# Fans.net
KiCad netlist of a schematic drawn in Altium Designer
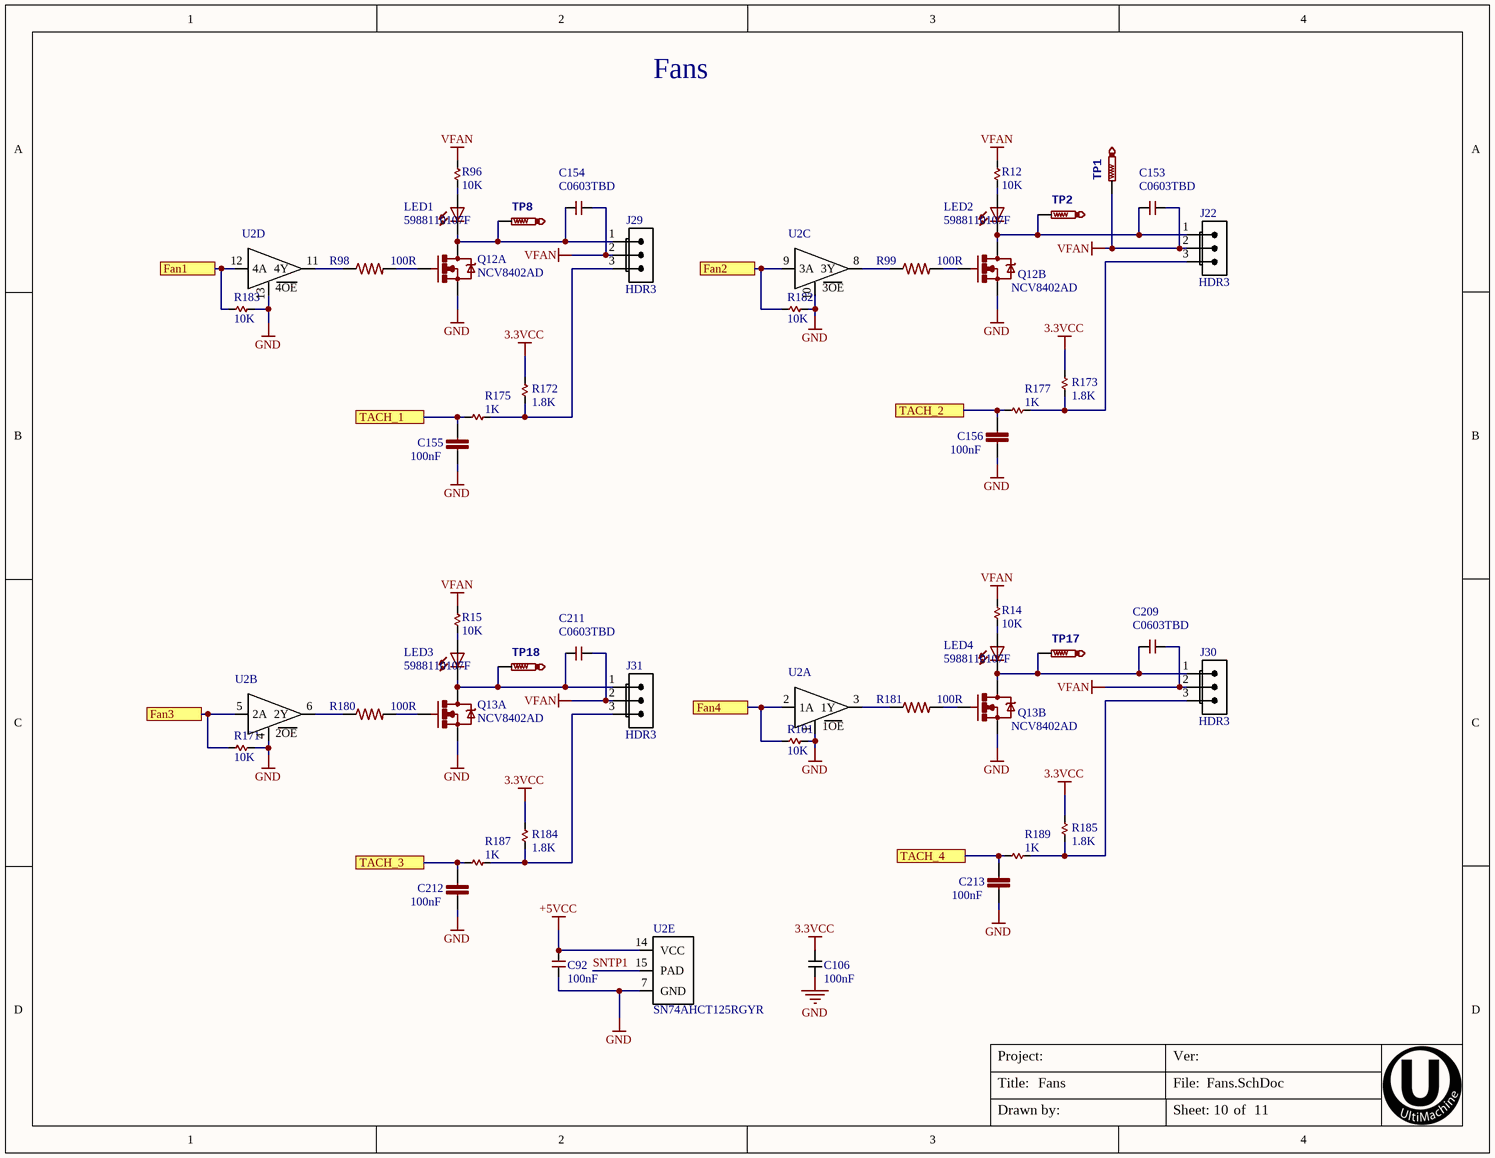
[diagram p0: Fans.SchDoc]

(export (version "E")
  (design (tool "Eeschema 10.0.6"))
  (components
    (comp (ref "C92")
      (value "100nF")
      (footprint "C0402")
      (description "CAP CER 0402 100nF 16V 10% X7R")
      (fields (field (name "MANUFACTURER") "Murata") (field (name "PART") "GRM155R71C104KA88D"))
      (libsource (lib "Capacitors") (part "100nF 0402 16V X7R"))
    )
    (comp (ref "C106")
      (value "100nF")
      (footprint "C0201 Large Pads")
      (description "CAP CER 0.1UF 6.3V 10% X5R 0201")
      (fields (field (name "PART") "CL03A104KQ3NNNC") (field (name "MANUFACTURER") "Samsung"))
      (libsource (lib "Capacitors") (part "100nF 6.3V X5R 0201"))
    )
    (comp (ref "C153")
      (value "C0603TBD")
      (footprint "C0603")
      (description "Capacitor Non Polarized")
      (fields (field (name "PART") "DNI-C0603TBD"))
      (libsource (lib "Capacitors") (part "C0603TBD"))
    )
    (comp (ref "C154")
      (value "C0603TBD")
      (footprint "C0603")
      (description "Capacitor Non Polarized")
      (fields (field (name "PART") "DNI-C0603TBD"))
      (libsource (lib "Capacitors") (part "C0603TBD"))
    )
    (comp (ref "C155")
      (value "100nF")
      (footprint "C0402")
      (description "CAP CER 0402 100nF 16V 10% X7R")
      (fields (field (name "MANUFACTURER") "Murata") (field (name "PART") "GRM155R71C104KA88D"))
      (libsource (lib "3Delight") (part "GRM155R71C104KA88D"))
    )
    (comp (ref "C156")
      (value "100nF")
      (footprint "C0402")
      (description "CAP CER 0402 100nF 16V 10% X7R")
      (fields (field (name "MANUFACTURER") "Murata") (field (name "PART") "GRM155R71C104KA88D"))
      (libsource (lib "3Delight") (part "GRM155R71C104KA88D"))
    )
    (comp (ref "C209")
      (value "C0603TBD")
      (footprint "C0603")
      (description "Capacitor Non Polarized")
      (fields (field (name "PART") "DNI-C0603TBD"))
      (libsource (lib "Capacitors") (part "C0603TBD"))
    )
    (comp (ref "C211")
      (value "C0603TBD")
      (footprint "C0603")
      (description "Capacitor Non Polarized")
      (fields (field (name "PART") "DNI-C0603TBD"))
      (libsource (lib "Capacitors") (part "C0603TBD"))
    )
    (comp (ref "C212")
      (value "100nF")
      (footprint "C0402")
      (description "CAP CER 0402 100nF 16V 10% X7R")
      (fields (field (name "MANUFACTURER") "Murata") (field (name "PART") "GRM155R71C104KA88D"))
      (libsource (lib "3Delight") (part "GRM155R71C104KA88D"))
    )
    (comp (ref "C213")
      (value "100nF")
      (footprint "C0402")
      (description "CAP CER 0402 100nF 16V 10% X7R")
      (fields (field (name "MANUFACTURER") "Murata") (field (name "PART") "GRM155R71C104KA88D"))
      (libsource (lib "3Delight") (part "GRM155R71C104KA88D"))
    )
    (comp (ref "J22")
      (value "HDR3")
      (footprint "70543-02 PIN-IN-PASTE")
      (description "3 Positions Header, Shrouded Connector 0.100\" (2.54mm) Through Hole Gold - Pin in Paste")
      (fields (field (name "MANUFACTURER") "Molex") (field (name "PART") "0705430002"))
      (libsource (lib "Connectors") (part "CONN 3POS VERT 0.1{dblquote} SHRD LOCKING PIP"))
    )
    (comp (ref "J29")
      (value "HDR3")
      (footprint "70543-02 PIN-IN-PASTE")
      (description "3 Positions Header, Shrouded Connector 0.100\" (2.54mm) Through Hole Gold - Pin in Paste")
      (fields (field (name "MANUFACTURER") "Molex") (field (name "PART") "0705430002"))
      (libsource (lib "Connectors") (part "CONN 3POS VERT 0.1{dblquote} SHRD LOCKING PIP"))
    )
    (comp (ref "J30")
      (value "HDR3")
      (footprint "70543-02 PIN-IN-PASTE")
      (description "3 Positions Header, Shrouded Connector 0.100\" (2.54mm) Through Hole Gold - Pin in Paste")
      (fields (field (name "MANUFACTURER") "Molex") (field (name "PART") "0705430002"))
      (libsource (lib "Connectors") (part "CONN 3POS VERT 0.1{dblquote} SHRD LOCKING PIP"))
    )
    (comp (ref "J31")
      (value "HDR3")
      (footprint "70543-02 PIN-IN-PASTE")
      (description "3 Positions Header, Shrouded Connector 0.100\" (2.54mm) Through Hole Gold - Pin in Paste")
      (fields (field (name "MANUFACTURER") "Molex") (field (name "PART") "0705430002"))
      (libsource (lib "Connectors") (part "CONN 3POS VERT 0.1{dblquote} SHRD LOCKING PIP"))
    )
    (comp (ref "LED1")
      (value "RED")
      (footprint "LED2012120")
      (description "LED 0805 Red")
      (fields
        (field (name "MANUFACTURER") "Dialight")
        (field (name "PART") "5988110107F")
        (field (name "TOLERANCE") "NA")
      )
      (libsource (lib "3Delight") (part "5988110107F"))
    )
    (comp (ref "LED2")
      (value "RED")
      (footprint "LED2012120")
      (description "LED 0805 Red")
      (fields
        (field (name "MANUFACTURER") "Dialight")
        (field (name "PART") "5988110107F")
        (field (name "TOLERANCE") "NA")
      )
      (libsource (lib "3Delight") (part "5988110107F"))
    )
    (comp (ref "LED3")
      (value "RED")
      (footprint "LED2012120")
      (description "LED 0805 Red")
      (fields
        (field (name "MANUFACTURER") "Dialight")
        (field (name "PART") "5988110107F")
        (field (name "TOLERANCE") "NA")
      )
      (libsource (lib "3Delight") (part "5988110107F"))
    )
    (comp (ref "LED4")
      (value "RED")
      (footprint "LED2012120")
      (description "LED 0805 Red")
      (fields
        (field (name "MANUFACTURER") "Dialight")
        (field (name "PART") "5988110107F")
        (field (name "TOLERANCE") "NA")
      )
      (libsource (lib "3Delight") (part "5988110107F"))
    )
    (comp (ref "Q12")
      (value "NCV8402AD")
      (footprint "NCV8402AD-SOIC8")
      (description "IC DVR LOW SIDE 8-SOIC")
      (fields (field (name "MANUFACTURER") "On Semi") (field (name "PART") "NCV8402ADDR2G"))
      (libsource (lib "Transistors") (part "NCV8402AD"))
    )
    (comp (ref "Q13")
      (value "NCV8402AD")
      (footprint "NCV8402AD-SOIC8")
      (description "IC DVR LOW SIDE 8-SOIC")
      (fields (field (name "MANUFACTURER") "On Semi") (field (name "PART") "NCV8402ADDR2G"))
      (libsource (lib "Transistors") (part "NCV8402AD"))
    )
    (comp (ref "R12")
      (value "10K")
      (footprint "R0402")
      (description "RES SMD 10K OHM 1% 1/16W 0402")
      (fields (field (name "MANUFACTURER") "Yageo") (field (name "PART") "RC0402FR-0710KP"))
      (libsource (lib "Resistors") (part "10k 1% 0402"))
    )
    (comp (ref "R14")
      (value "10K")
      (footprint "R0402")
      (description "RES SMD 10K OHM 1% 1/16W 0402")
      (fields (field (name "MANUFACTURER") "Yageo") (field (name "PART") "RC0402FR-0710KP"))
      (libsource (lib "Resistors") (part "10k 1% 0402"))
    )
    (comp (ref "R15")
      (value "10K")
      (footprint "R0402")
      (description "RES SMD 10K OHM 1% 1/16W 0402")
      (fields (field (name "MANUFACTURER") "Yageo") (field (name "PART") "RC0402FR-0710KP"))
      (libsource (lib "Resistors") (part "10k 1% 0402"))
    )
    (comp (ref "R96")
      (value "10K")
      (footprint "R0402")
      (description "RES SMD 10K OHM 1% 1/16W 0402")
      (fields (field (name "MANUFACTURER") "Yageo") (field (name "PART") "RC0402FR-0710KP"))
      (libsource (lib "Resistors") (part "10k 1% 0402"))
    )
    (comp (ref "R98")
      (value "100R")
      (footprint "R0402")
      (description "RES SMD 100 OHM 1% 1/16W 0402")
      (fields (field (name "MANUFACTURER") "Yageo") (field (name "PART") "RC0402FR-07100RL"))
      (libsource (lib "Archim") (part "RES 100R 0402 1%"))
    )
    (comp (ref "R99")
      (value "100R")
      (footprint "R0402")
      (description "RES SMD 100 OHM 1% 1/16W 0402")
      (fields (field (name "MANUFACTURER") "Yageo") (field (name "PART") "RC0402FR-07100RL"))
      (libsource (lib "Archim") (part "RES 100R 0402 1%"))
    )
    (comp (ref "R101")
      (value "10K")
      (footprint "R0402")
      (description "RES SMD 10K OHM 1% 1/16W 0402")
      (fields (field (name "MANUFACTURER") "Yageo") (field (name "PART") "RC0402FR-0710KP"))
      (libsource (lib "Resistors") (part "10k 1% 0402"))
    )
    (comp (ref "R171")
      (value "10K")
      (footprint "R0402")
      (description "RES SMD 10K OHM 1% 1/16W 0402")
      (fields (field (name "MANUFACTURER") "Yageo") (field (name "PART") "RC0402FR-0710KP"))
      (libsource (lib "Resistors") (part "10k 1% 0402"))
    )
    (comp (ref "R172")
      (value "1.8K")
      (footprint "R0402")
      (description "RES SMD 1.8K OHM 1% 1/16W 0402")
      (fields (field (name "MANUFACTURER") "Yageo") (field (name "PART") "RC0402FR-071K8L"))
      (libsource (lib "3Delight") (part "RC0402FR-071K8L"))
    )
    (comp (ref "R173")
      (value "1.8K")
      (footprint "R0402")
      (description "RES SMD 1.8K OHM 1% 1/16W 0402")
      (fields (field (name "MANUFACTURER") "Yageo") (field (name "PART") "RC0402FR-071K8L"))
      (libsource (lib "3Delight") (part "RC0402FR-071K8L"))
    )
    (comp (ref "R175")
      (value "1K")
      (footprint "R0402")
      (description "RES SMD 1K OHM 1% 1/16W 0402")
      (fields (field (name "MANUFACTURER") "Yageo") (field (name "PART") "RC0402FR-071KL"))
      (libsource (lib "3Delight") (part "RC0402FR-071KL"))
    )
    (comp (ref "R177")
      (value "1K")
      (footprint "R0402")
      (description "RES SMD 1K OHM 1% 1/16W 0402")
      (fields (field (name "MANUFACTURER") "Yageo") (field (name "PART") "RC0402FR-071KL"))
      (libsource (lib "3Delight") (part "RC0402FR-071KL"))
    )
    (comp (ref "R180")
      (value "100R")
      (footprint "R0402")
      (description "RES SMD 100 OHM 1% 1/16W 0402")
      (fields (field (name "MANUFACTURER") "Yageo") (field (name "PART") "RC0402FR-07100RL"))
      (libsource (lib "Archim") (part "RES 100R 0402 1%"))
    )
    (comp (ref "R181")
      (value "100R")
      (footprint "R0402")
      (description "RES SMD 100 OHM 1% 1/16W 0402")
      (fields (field (name "MANUFACTURER") "Yageo") (field (name "PART") "RC0402FR-07100RL"))
      (libsource (lib "Archim") (part "RES 100R 0402 1%"))
    )
    (comp (ref "R182")
      (value "10K")
      (footprint "R0402")
      (description "RES SMD 10K OHM 1% 1/16W 0402")
      (fields (field (name "MANUFACTURER") "Yageo") (field (name "PART") "RC0402FR-0710KP"))
      (libsource (lib "Resistors") (part "10k 1% 0402"))
    )
    (comp (ref "R183")
      (value "10K")
      (footprint "R0402")
      (description "RES SMD 10K OHM 1% 1/16W 0402")
      (fields (field (name "MANUFACTURER") "Yageo") (field (name "PART") "RC0402FR-0710KP"))
      (libsource (lib "Resistors") (part "10k 1% 0402"))
    )
    (comp (ref "R184")
      (value "1.8K")
      (footprint "R0402")
      (description "RES SMD 1.8K OHM 1% 1/16W 0402")
      (fields (field (name "MANUFACTURER") "Yageo") (field (name "PART") "RC0402FR-071K8L"))
      (libsource (lib "3Delight") (part "RC0402FR-071K8L"))
    )
    (comp (ref "R185")
      (value "1.8K")
      (footprint "R0402")
      (description "RES SMD 1.8K OHM 1% 1/16W 0402")
      (fields (field (name "MANUFACTURER") "Yageo") (field (name "PART") "RC0402FR-071K8L"))
      (libsource (lib "3Delight") (part "RC0402FR-071K8L"))
    )
    (comp (ref "R187")
      (value "1K")
      (footprint "R0402")
      (description "RES SMD 1K OHM 1% 1/16W 0402")
      (fields (field (name "MANUFACTURER") "Yageo") (field (name "PART") "RC0402FR-071KL"))
      (libsource (lib "3Delight") (part "RC0402FR-071KL"))
    )
    (comp (ref "R189")
      (value "1K")
      (footprint "R0402")
      (description "RES SMD 1K OHM 1% 1/16W 0402")
      (fields (field (name "MANUFACTURER") "Yageo") (field (name "PART") "RC0402FR-071KL"))
      (libsource (lib "3Delight") (part "RC0402FR-071KL"))
    )
    (comp (ref "TP1")
      (value "TestPoint")
      (footprint "TP1-27")
      (description "Test Point")
      (libsource (lib "") (part "TestPoint_1"))
    )
    (comp (ref "TP2")
      (value "TestPoint")
      (footprint "TP1-27")
      (description "Test Point")
      (libsource (lib "3Delight") (part "TestPoint"))
    )
    (comp (ref "TP8")
      (value "TestPoint")
      (footprint "TP1-27")
      (description "Test Point")
      (libsource (lib "3Delight") (part "TestPoint"))
    )
    (comp (ref "TP17")
      (value "TestPoint")
      (footprint "TP1-27")
      (description "Test Point")
      (libsource (lib "3Delight") (part "TestPoint"))
    )
    (comp (ref "TP18")
      (value "TestPoint")
      (footprint "TP1-27")
      (description "Test Point")
      (libsource (lib "3Delight") (part "TestPoint"))
    )
    (comp (ref "U2")
      (value "SN74AHCT125RGYR")
      (footprint "QFN50P350X350X100_RGY_S-PVQFN-N14")
      (description "Quadruple Bus Buffer Gates With 3-State Outputs 14-VQFN -40 to 125")
      (fields (field (name "MANUFACTURER") "Texas Instruments") (field (name "TOLERANCE") "-NA-"))
      (libsource (lib "ICs-Logic") (part "SN74AHCT125"))
    )
  )
  (nets
    (net (code "1") (name "+5VCC") (class "Default")
      (node (ref "C92") (pin "2") (pinfunction "2_2") (pintype "passive"))
      (node (ref "U2") (pin "14") (pinfunction "VCC_14") (pintype "passive"))
    )
    (net (code "2") (name "/Fan1") (class "Default")
      (node (ref "R183") (pin "1") (pinfunction "1_1") (pintype "passive"))
      (node (ref "U2") (pin "12") (pinfunction "4A_12") (pintype "passive"))
    )
    (net (code "3") (name "/Fan2") (class "Default")
      (node (ref "R182") (pin "1") (pinfunction "1_1") (pintype "passive"))
      (node (ref "U2") (pin "9") (pinfunction "3A_9") (pintype "passive"))
    )
    (net (code "4") (name "/Fan3") (class "Default")
      (node (ref "R171") (pin "1") (pinfunction "1_1") (pintype "passive"))
      (node (ref "U2") (pin "5") (pinfunction "2A_5") (pintype "passive"))
    )
    (net (code "5") (name "/Fan4") (class "Default")
      (node (ref "R101") (pin "1") (pinfunction "1_1") (pintype "passive"))
      (node (ref "U2") (pin "2") (pinfunction "1A_2") (pintype "passive"))
    )
    (net (code "6") (name "/SNTP1") (class "Default")
      (node (ref "U2") (pin "15") (pinfunction "PAD_15") (pintype "passive"))
    )
    (net (code "7") (name "/TACH_1") (class "Default")
      (node (ref "C155") (pin "1") (pinfunction "1_1") (pintype "passive"))
      (node (ref "R175") (pin "1") (pinfunction "1_1") (pintype "passive"))
    )
    (net (code "8") (name "/TACH_2") (class "Default")
      (node (ref "C156") (pin "1") (pinfunction "1_1") (pintype "passive"))
      (node (ref "R177") (pin "1") (pinfunction "1_1") (pintype "passive"))
    )
    (net (code "9") (name "/TACH_3") (class "Default")
      (node (ref "C212") (pin "1") (pinfunction "1_1") (pintype "passive"))
      (node (ref "R187") (pin "1") (pinfunction "1_1") (pintype "passive"))
    )
    (net (code "10") (name "/TACH_4") (class "Default")
      (node (ref "C213") (pin "1") (pinfunction "1_1") (pintype "passive"))
      (node (ref "R189") (pin "1") (pinfunction "1_1") (pintype "passive"))
    )
    (net (code "11") (name "3.3VCC") (class "Default")
      (node (ref "C106") (pin "2") (pinfunction "2_2") (pintype "passive"))
      (node (ref "R172") (pin "2") (pinfunction "2_2") (pintype "passive"))
      (node (ref "R173") (pin "2") (pinfunction "2_2") (pintype "passive"))
      (node (ref "R184") (pin "2") (pinfunction "2_2") (pintype "passive"))
      (node (ref "R185") (pin "2") (pinfunction "2_2") (pintype "passive"))
    )
    (net (code "12") (name "GND") (class "Default")
      (node (ref "C106") (pin "1") (pinfunction "1_1") (pintype "passive"))
      (node (ref "C155") (pin "2") (pinfunction "2_2") (pintype "passive"))
      (node (ref "C156") (pin "2") (pinfunction "2_2") (pintype "passive"))
      (node (ref "C212") (pin "2") (pinfunction "2_2") (pintype "passive"))
      (node (ref "C213") (pin "2") (pinfunction "2_2") (pintype "passive"))
      (node (ref "C92") (pin "1") (pinfunction "1_1") (pintype "passive"))
      (node (ref "Q12") (pin "1") (pinfunction "S_1") (pintype "passive"))
      (node (ref "Q12") (pin "3") (pinfunction "S_3") (pintype "passive"))
      (node (ref "Q13") (pin "1") (pinfunction "S_1") (pintype "passive"))
      (node (ref "Q13") (pin "3") (pinfunction "S_3") (pintype "passive"))
      (node (ref "R101") (pin "2") (pinfunction "2_2") (pintype "passive"))
      (node (ref "R171") (pin "2") (pinfunction "2_2") (pintype "passive"))
      (node (ref "R182") (pin "2") (pinfunction "2_2") (pintype "passive"))
      (node (ref "R183") (pin "2") (pinfunction "2_2") (pintype "passive"))
      (node (ref "U2") (pin "1") (pinfunction "1OE_1") (pintype "passive"))
      (node (ref "U2") (pin "10") (pinfunction "3OE_10") (pintype "passive"))
      (node (ref "U2") (pin "13") (pinfunction "4OE_13") (pintype "passive"))
      (node (ref "U2") (pin "4") (pinfunction "2OE_4") (pintype "passive"))
      (node (ref "U2") (pin "7") (pinfunction "GND_7") (pintype "passive"))
    )
    (net (code "13") (name "Net-(J22-S-Pad3)") (class "Default")
      (node (ref "J22") (pin "3") (pinfunction "S_3") (pintype "passive"))
      (node (ref "R173") (pin "1") (pinfunction "1_1") (pintype "passive"))
      (node (ref "R177") (pin "2") (pinfunction "2_2") (pintype "passive"))
    )
    (net (code "14") (name "Net-(J29-S-Pad3)") (class "Default")
      (node (ref "J29") (pin "3") (pinfunction "S_3") (pintype "passive"))
      (node (ref "R172") (pin "1") (pinfunction "1_1") (pintype "passive"))
      (node (ref "R175") (pin "2") (pinfunction "2_2") (pintype "passive"))
    )
    (net (code "15") (name "Net-(J30-S-Pad3)") (class "Default")
      (node (ref "J30") (pin "3") (pinfunction "S_3") (pintype "passive"))
      (node (ref "R185") (pin "1") (pinfunction "1_1") (pintype "passive"))
      (node (ref "R189") (pin "2") (pinfunction "2_2") (pintype "passive"))
    )
    (net (code "16") (name "Net-(J31-S-Pad3)") (class "Default")
      (node (ref "J31") (pin "3") (pinfunction "S_3") (pintype "passive"))
      (node (ref "R184") (pin "1") (pinfunction "1_1") (pintype "passive"))
      (node (ref "R187") (pin "2") (pinfunction "2_2") (pintype "passive"))
    )
    (net (code "17") (name "Net-(LED1-PadA)") (class "Default")
      (node (ref "LED1") (pin "A") (pinfunction "A_A") (pintype "passive"))
      (node (ref "R96") (pin "1") (pinfunction "1_1") (pintype "passive"))
    )
    (net (code "18") (name "Net-(LED2-PadA)") (class "Default")
      (node (ref "LED2") (pin "A") (pinfunction "A_A") (pintype "passive"))
      (node (ref "R12") (pin "1") (pinfunction "1_1") (pintype "passive"))
    )
    (net (code "19") (name "Net-(LED3-PadA)") (class "Default")
      (node (ref "LED3") (pin "A") (pinfunction "A_A") (pintype "passive"))
      (node (ref "R15") (pin "1") (pinfunction "1_1") (pintype "passive"))
    )
    (net (code "20") (name "Net-(LED4-PadA)") (class "Default")
      (node (ref "LED4") (pin "A") (pinfunction "A_A") (pintype "passive"))
      (node (ref "R14") (pin "1") (pinfunction "1_1") (pintype "passive"))
    )
    (net (code "21") (name "Net-(Q12A-D)") (class "Default")
      (node (ref "C154") (pin "2") (pinfunction "2_2") (pintype "passive"))
      (node (ref "J29") (pin "1") (pinfunction "S_1") (pintype "passive"))
      (node (ref "LED1") (pin "C") (pinfunction "C_C") (pintype "passive"))
      (node (ref "Q12") (pin "7") (pinfunction "D_7") (pintype "passive"))
      (node (ref "TP8") (pin "TP") (pinfunction "TP_TP") (pintype "passive"))
    )
    (net (code "22") (name "Net-(Q12A-G)") (class "Default")
      (node (ref "Q12") (pin "2") (pinfunction "G_2") (pintype "passive"))
      (node (ref "R98") (pin "2") (pinfunction "2_2") (pintype "passive"))
    )
    (net (code "23") (name "Net-(Q12B-D)") (class "Default")
      (node (ref "C153") (pin "2") (pinfunction "2_2") (pintype "passive"))
      (node (ref "J22") (pin "1") (pinfunction "S_1") (pintype "passive"))
      (node (ref "LED2") (pin "C") (pinfunction "C_C") (pintype "passive"))
      (node (ref "Q12") (pin "5") (pinfunction "D_5") (pintype "passive"))
      (node (ref "TP2") (pin "TP") (pinfunction "TP_TP") (pintype "passive"))
    )
    (net (code "24") (name "Net-(Q12B-G)") (class "Default")
      (node (ref "Q12") (pin "4") (pinfunction "G_4") (pintype "passive"))
      (node (ref "R99") (pin "2") (pinfunction "2_2") (pintype "passive"))
    )
    (net (code "25") (name "Net-(Q13A-D)") (class "Default")
      (node (ref "C211") (pin "2") (pinfunction "2_2") (pintype "passive"))
      (node (ref "J31") (pin "1") (pinfunction "S_1") (pintype "passive"))
      (node (ref "LED3") (pin "C") (pinfunction "C_C") (pintype "passive"))
      (node (ref "Q13") (pin "7") (pinfunction "D_7") (pintype "passive"))
      (node (ref "TP18") (pin "TP") (pinfunction "TP_TP") (pintype "passive"))
    )
    (net (code "26") (name "Net-(Q13A-G)") (class "Default")
      (node (ref "Q13") (pin "2") (pinfunction "G_2") (pintype "passive"))
      (node (ref "R180") (pin "2") (pinfunction "2_2") (pintype "passive"))
    )
    (net (code "27") (name "Net-(Q13B-D)") (class "Default")
      (node (ref "C209") (pin "2") (pinfunction "2_2") (pintype "passive"))
      (node (ref "J30") (pin "1") (pinfunction "S_1") (pintype "passive"))
      (node (ref "LED4") (pin "C") (pinfunction "C_C") (pintype "passive"))
      (node (ref "Q13") (pin "5") (pinfunction "D_5") (pintype "passive"))
      (node (ref "TP17") (pin "TP") (pinfunction "TP_TP") (pintype "passive"))
    )
    (net (code "28") (name "Net-(Q13B-G)") (class "Default")
      (node (ref "Q13") (pin "4") (pinfunction "G_4") (pintype "passive"))
      (node (ref "R181") (pin "2") (pinfunction "2_2") (pintype "passive"))
    )
    (net (code "29") (name "Net-(U2A-1Y)") (class "Default")
      (node (ref "R181") (pin "1") (pinfunction "1_1") (pintype "passive"))
      (node (ref "U2") (pin "3") (pinfunction "1Y_3") (pintype "passive"))
    )
    (net (code "30") (name "Net-(U2B-2Y)") (class "Default")
      (node (ref "R180") (pin "1") (pinfunction "1_1") (pintype "passive"))
      (node (ref "U2") (pin "6") (pinfunction "2Y_6") (pintype "passive"))
    )
    (net (code "31") (name "Net-(U2C-3Y)") (class "Default")
      (node (ref "R99") (pin "1") (pinfunction "1_1") (pintype "passive"))
      (node (ref "U2") (pin "8") (pinfunction "3Y_8") (pintype "passive"))
    )
    (net (code "32") (name "Net-(U2D-4Y)") (class "Default")
      (node (ref "R98") (pin "1") (pinfunction "1_1") (pintype "passive"))
      (node (ref "U2") (pin "11") (pinfunction "4Y_11") (pintype "passive"))
    )
    (net (code "33") (name "VFAN") (class "Default")
      (node (ref "C153") (pin "1") (pinfunction "1_1") (pintype "passive"))
      (node (ref "C154") (pin "1") (pinfunction "1_1") (pintype "passive"))
      (node (ref "C209") (pin "1") (pinfunction "1_1") (pintype "passive"))
      (node (ref "C211") (pin "1") (pinfunction "1_1") (pintype "passive"))
      (node (ref "J22") (pin "2") (pinfunction "S_2") (pintype "passive"))
      (node (ref "J29") (pin "2") (pinfunction "S_2") (pintype "passive"))
      (node (ref "J30") (pin "2") (pinfunction "S_2") (pintype "passive"))
      (node (ref "J31") (pin "2") (pinfunction "S_2") (pintype "passive"))
      (node (ref "R12") (pin "2") (pinfunction "2_2") (pintype "passive"))
      (node (ref "R14") (pin "2") (pinfunction "2_2") (pintype "passive"))
      (node (ref "R15") (pin "2") (pinfunction "2_2") (pintype "passive"))
      (node (ref "R96") (pin "2") (pinfunction "2_2") (pintype "passive"))
      (node (ref "TP1") (pin "TP") (pinfunction "TP_TP") (pintype "passive"))
    )
  )
)
